# ai_breakout_stereojack.net
KiCad netlist of a schematic drawn in EAGLE
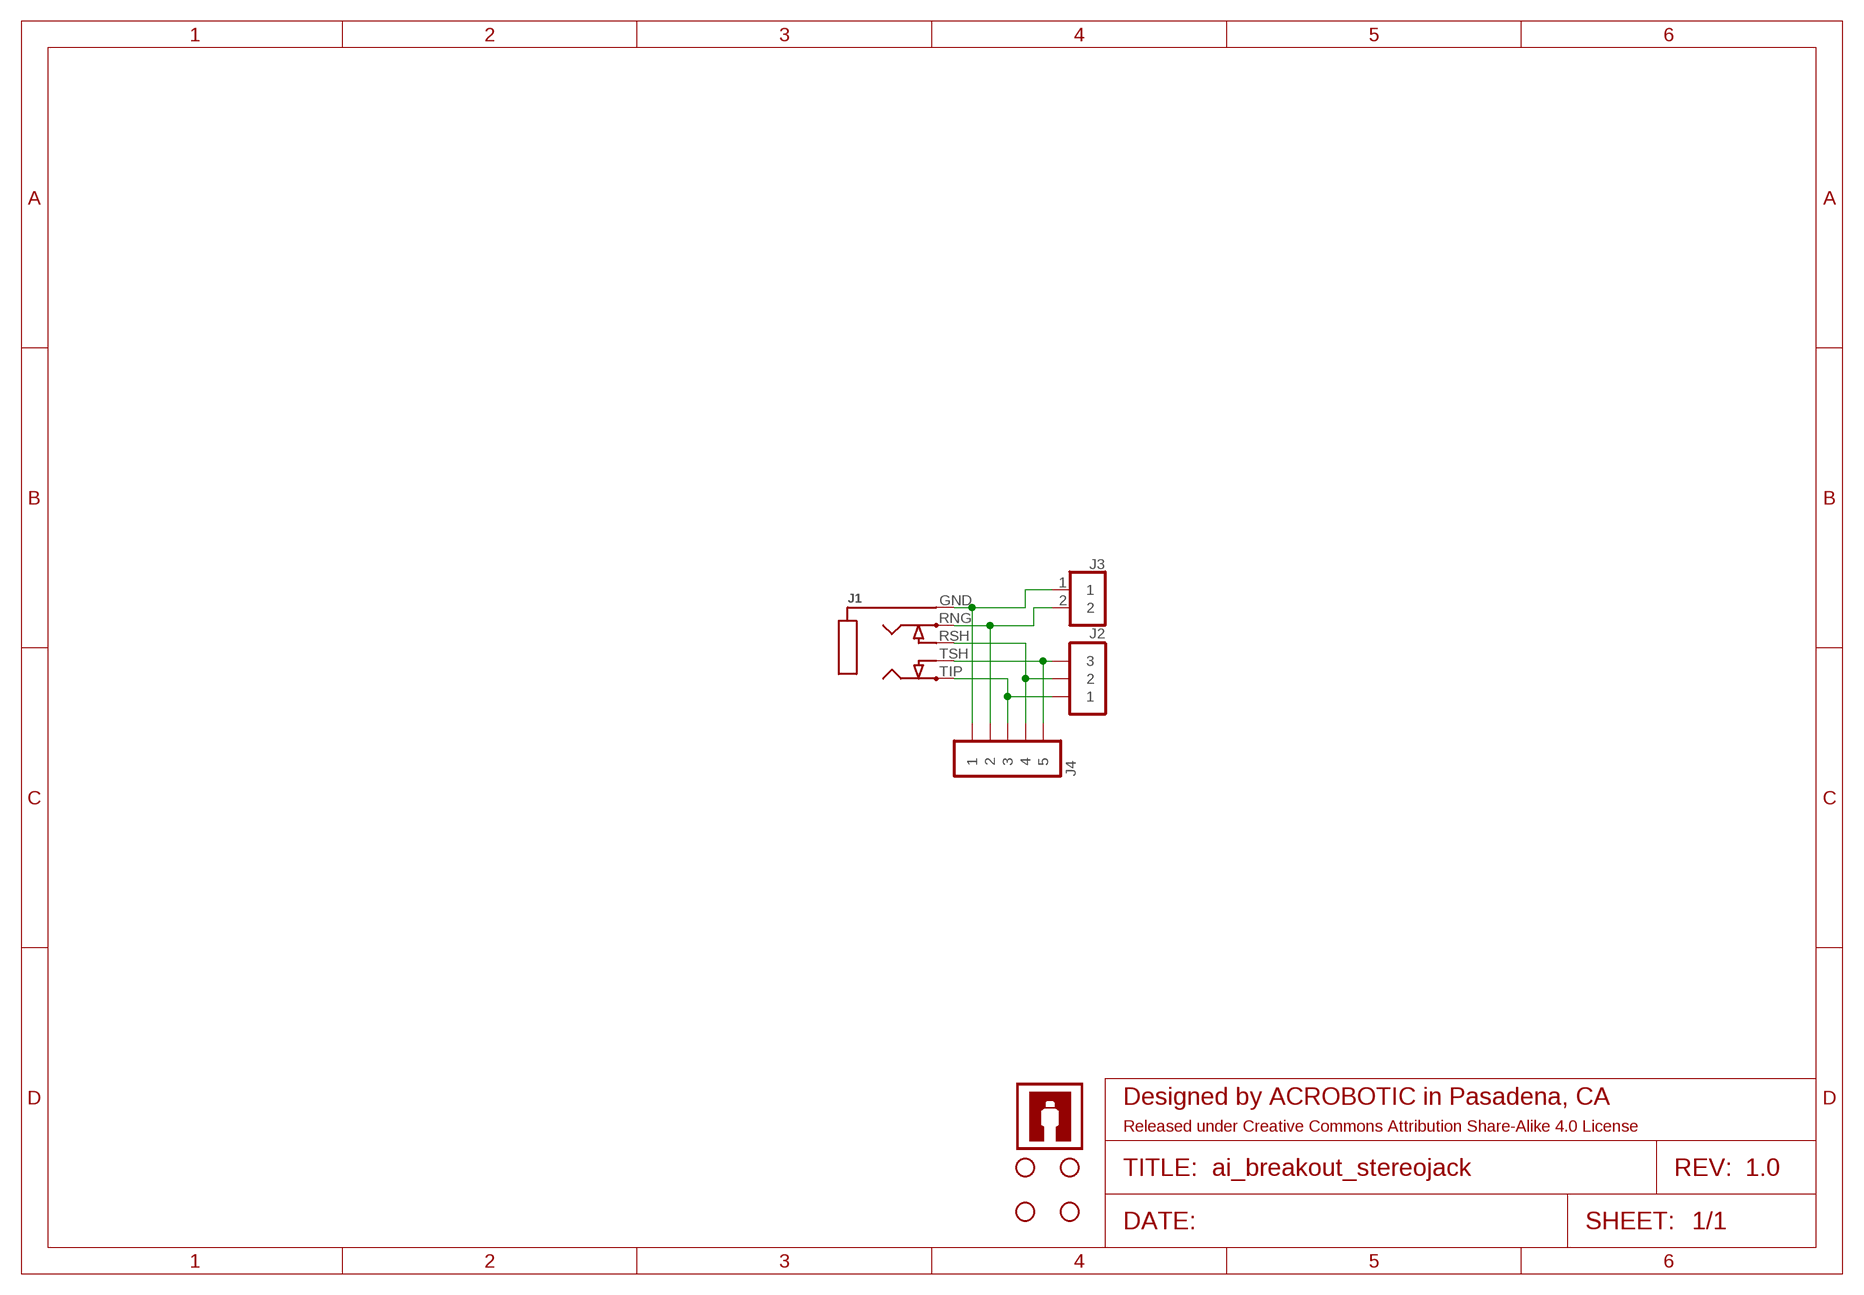
[diagram p0: schematic, sheet 1]

(export (version "E")
  (design (tool "Eeschema 10.0.6"))
  (components
    (comp (ref "FRAME1")
      (value "FRAME-LETTER")
      (footprint "eagle-import:CREATIVE-COMMONS")
      (fields (field (name "REV") "1.0"))
      (libsource (lib "eagle-import") (part "FRAME-LETTER"))
    )
    (comp (ref "J1")
      (value "STEREOJACKSJ1-351XNG")
      (footprint "eagle-import:SJ1-351XNG")
      (libsource (lib "eagle-import") (part "STEREOJACKSJ1-351XNG"))
    )
    (comp (ref "J2")
      (value "1X03ST")
      (footprint "eagle-import:1X03-ST")
      (libsource (lib "eagle-import") (part "1X03ST"))
    )
    (comp (ref "J3")
      (value "1X02ST")
      (footprint "eagle-import:1X02-ST")
      (libsource (lib "eagle-import") (part "1X02ST"))
    )
    (comp (ref "J4")
      (value "1X05")
      (footprint "eagle-import:1X05")
      (libsource (lib "eagle-import") (part "1X05"))
    )
    (comp (ref "STANDOFF1")
      (value "STAND-OFF4")
      (footprint "eagle-import:STAND-OFF-4")
      (libsource (lib "eagle-import") (part "STAND-OFF4"))
    )
    (comp (ref "STANDOFF2")
      (value "STAND-OFF4")
      (footprint "eagle-import:STAND-OFF-4")
      (libsource (lib "eagle-import") (part "STAND-OFF4"))
    )
    (comp (ref "STANDOFF3")
      (value "STAND-OFF4")
      (footprint "eagle-import:STAND-OFF-4")
      (libsource (lib "eagle-import") (part "STAND-OFF4"))
    )
    (comp (ref "STANDOFF4")
      (value "STAND-OFF4")
      (footprint "eagle-import:STAND-OFF-4")
      (libsource (lib "eagle-import") (part "STAND-OFF4"))
    )
    (comp (ref "U$1")
      (value "AI-LOGOXS")
      (footprint "eagle-import:AI-LOGO-XS")
      (libsource (lib "eagle-import") (part "AI-LOGOXS"))
    )
    (comp (ref "U$2")
      (value "AI-LOGOXS")
      (footprint "eagle-import:AI-LOGO-XS")
      (libsource (lib "eagle-import") (part "AI-LOGOXS"))
    )
  )
  (nets
    (net (code "1") (name "Net-(J1-PadGND)") (class "Default")
      (node (ref "J1") (pin "GND") (pinfunction "GND_GND") (pintype "passive"))
      (node (ref "J3") (pin "1") (pinfunction "1_1") (pintype "bidirectional"))
      (node (ref "J4") (pin "1") (pinfunction "1_1") (pintype "bidirectional"))
    )
    (net (code "2") (name "Net-(J1-PadRNG)") (class "Default")
      (node (ref "J1") (pin "RNG") (pinfunction "RNG_RNG") (pintype "passive"))
      (node (ref "J3") (pin "2") (pinfunction "2_2") (pintype "bidirectional"))
      (node (ref "J4") (pin "2") (pinfunction "2_2") (pintype "bidirectional"))
    )
    (net (code "3") (name "Net-(J1-PadRSH)") (class "Default")
      (node (ref "J1") (pin "RSH") (pinfunction "RSH_RSH") (pintype "passive"))
      (node (ref "J2") (pin "2") (pinfunction "2_2") (pintype "bidirectional"))
      (node (ref "J4") (pin "4") (pinfunction "4_4") (pintype "bidirectional"))
    )
    (net (code "4") (name "Net-(J1-PadTIP)") (class "Default")
      (node (ref "J1") (pin "TIP") (pinfunction "TIP_TIP") (pintype "passive"))
      (node (ref "J2") (pin "1") (pinfunction "1_1") (pintype "bidirectional"))
      (node (ref "J4") (pin "3") (pinfunction "3_3") (pintype "bidirectional"))
    )
    (net (code "5") (name "Net-(J1-PadTSH)") (class "Default")
      (node (ref "J1") (pin "TSH") (pinfunction "TSH_TSH") (pintype "passive"))
      (node (ref "J2") (pin "3") (pinfunction "3_3") (pintype "bidirectional"))
      (node (ref "J4") (pin "5") (pinfunction "5_5") (pintype "bidirectional"))
    )
  )
)
